# bluetooth_bma400.net
KiCad netlist of a schematic drawn in EAGLE
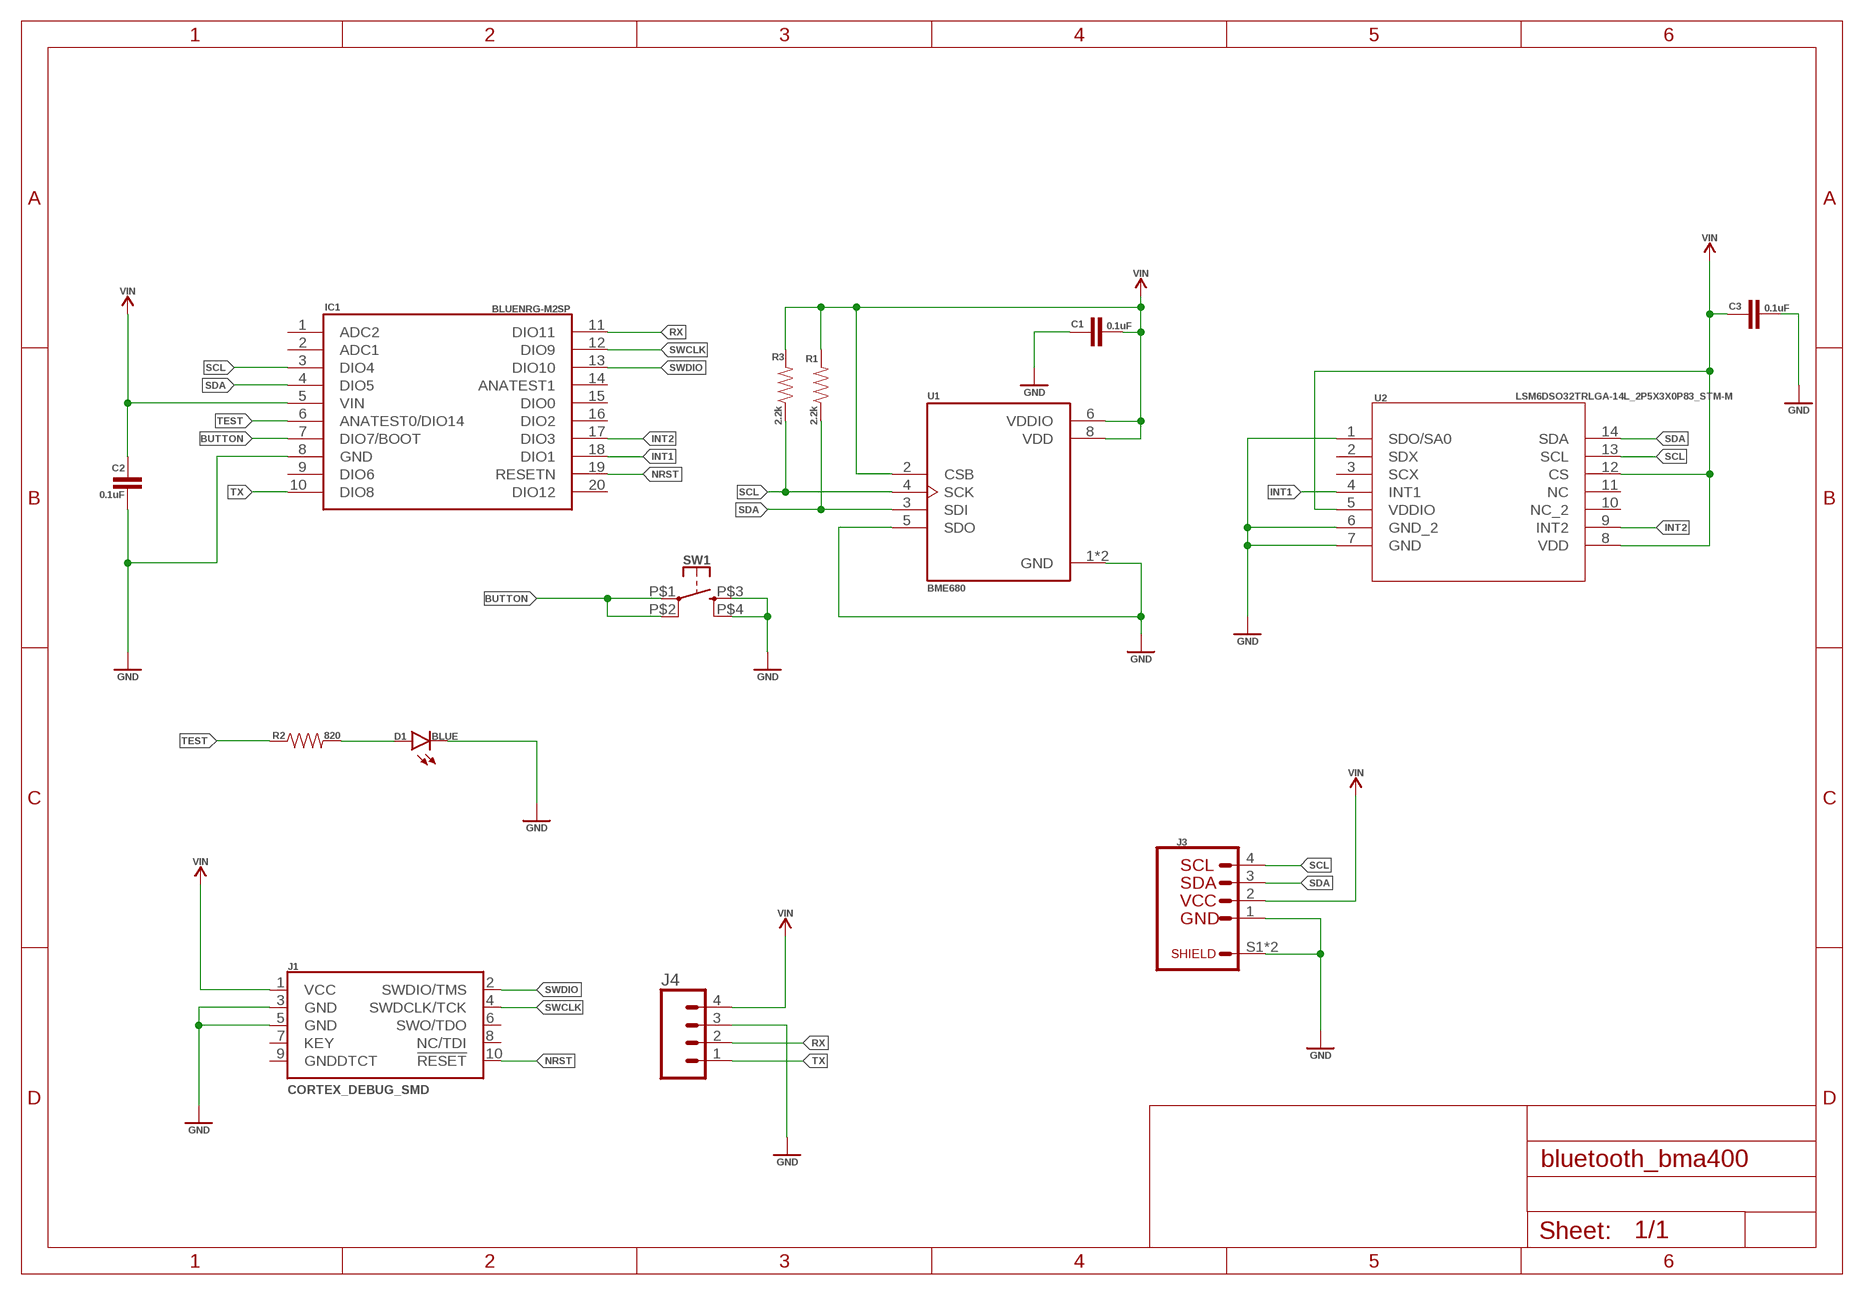
[diagram p0: schematic, sheet 1]

(export (version "E")
  (design (tool "Eeschema 10.0.6"))
  (components
    (comp (ref "C1")
      (value "0.1uF")
      (footprint "eagle-import:0603")
      (libsource (lib "eagle-import") (part "0.1UF-0603-25V-(+80/-20%)"))
    )
    (comp (ref "C2")
      (value "0.1uF")
      (footprint "eagle-import:0603")
      (libsource (lib "eagle-import") (part "0.1UF-0603-25V-(+80/-20%)"))
    )
    (comp (ref "C3")
      (value "0.1uF")
      (footprint "eagle-import:0603")
      (libsource (lib "eagle-import") (part "0.1UF-0603-25V-(+80/-20%)"))
    )
    (comp (ref "D1")
      (value "BLUE")
      (footprint "eagle-import:LED-0603")
      (libsource (lib "eagle-import") (part "LED-BLUE0603"))
    )
    (comp (ref "IC1")
      (value "BLUENRG-M2SP")
      (footprint "eagle-import:BLUENRGM2SP")
      (fields (field (name "MOUSER_PART_NUMBER") "511-BLUENRG-M2SP"))
      (libsource (lib "eagle-import") (part "BLUENRG-M2SP"))
    )
    (comp (ref "J1")
      (value "CORTEX_DEBUG_SMD")
      (footprint "eagle-import:SAMTECH_FTSH-105-01")
      (libsource (lib "eagle-import") (part "CORTEX_DEBUG_SMD"))
    )
    (comp (ref "J3")
      (value "QWIIC")
      (footprint "eagle-import:CONN_BM04B-SRSS-TB(LF)(SN)")
      (libsource (lib "eagle-import") (part "QWIIC"))
    )
    (comp (ref "J4")
      (value "CONN_04SMD")
      (footprint "eagle-import:1X04_SMD_RA_MALE")
      (libsource (lib "eagle-import") (part "CONN_04SMD"))
    )
    (comp (ref "R1")
      (value "2.2k")
      (footprint "eagle-import:0603")
      (libsource (lib "eagle-import") (part "2.2KOHM-0603-1/10W-1%"))
    )
    (comp (ref "R2")
      (value "820")
      (footprint "eagle-import:0603")
      (fields (field (name "SPICEPREFIX") "R"))
      (libsource (lib "eagle-import") (part "8.2KOHM-0603-1/10W-5%"))
    )
    (comp (ref "R3")
      (value "2.2k")
      (footprint "eagle-import:0603")
      (libsource (lib "eagle-import") (part "2.2KOHM-0603-1/10W-1%"))
    )
    (comp (ref "SW1")
      (value "REVERSE_SWITCH")
      (footprint "eagle-import:REVERSE_TACTILE")
      (libsource (lib "eagle-import") (part "REVERSE_SWITCH"))
    )
    (comp (ref "U1")
      (value "BME680")
      (footprint "eagle-import:PSON80P300X300X100-8N")
      (fields (field (name "MF") "Bosch Sensortec"))
      (libsource (lib "eagle-import") (part "BME680"))
    )
    (comp (ref "U2")
      (value "LSM6DSO32TRLGA-14L_2P5X3X0P83_STM-M")
      (footprint "eagle-import:LGA-14L_2P5X3X0P83_STM-M")
      (fields
        (field (name "MANUFACTURER_PART_NUMBER") "LSM6DSO32TR")
        (field (name "COPYRIGHT") "Copyright (C) 2022 Ultra Librarian. All rights reserved.")
      )
      (libsource (lib "eagle-import") (part "LSM6DSO32TRLGA-14L_2P5X3X0P83_STM-M"))
    )
  )
  (nets
    (net (code "1") (name "BUTTON") (class "Default")
      (node (ref "IC1") (pin "7") (pinfunction "DIO7/BOOT_7") (pintype "bidirectional"))
      (node (ref "SW1") (pin "P$1") (pinfunction "1_P$1") (pintype "passive"))
      (node (ref "SW1") (pin "P$2") (pinfunction "2_P$2") (pintype "passive"))
    )
    (net (code "2") (name "GND") (class "Default")
      (node (ref "C1") (pin "1") (pinfunction "1_1") (pintype "passive"))
      (node (ref "C2") (pin "2") (pinfunction "2_2") (pintype "passive"))
      (node (ref "C3") (pin "2") (pinfunction "2_2") (pintype "passive"))
      (node (ref "D1") (pin "C") (pinfunction "C_C") (pintype "passive"))
      (node (ref "IC1") (pin "8") (pinfunction "GND_8") (pintype "bidirectional"))
      (node (ref "J1") (pin "3") (pinfunction "GND_3") (pintype "bidirectional"))
      (node (ref "J1") (pin "5") (pinfunction "GND_5") (pintype "bidirectional"))
      (node (ref "J3") (pin "1") (pinfunction "1_1") (pintype "power_in"))
      (node (ref "J3") (pin "S1") (pinfunction "P$2_S1") (pintype "power_in"))
      (node (ref "J3") (pin "S2") (pinfunction "P$2_S2") (pintype "power_in"))
      (node (ref "J4") (pin "3") (pinfunction "SDA_3") (pintype "passive"))
      (node (ref "SW1") (pin "P$3") (pinfunction "3_P$3") (pintype "passive"))
      (node (ref "SW1") (pin "P$4") (pinfunction "4_P$4") (pintype "passive"))
      (node (ref "U1") (pin "1") (pinfunction "GND_1") (pintype "power_in"))
      (node (ref "U1") (pin "5") (pinfunction "SDO_5") (pintype "bidirectional"))
      (node (ref "U1") (pin "7") (pinfunction "GND_7") (pintype "power_in"))
      (node (ref "U2") (pin "1") (pinfunction "SDO/SA0_1") (pintype "bidirectional"))
      (node (ref "U2") (pin "6") (pinfunction "GND_2_6") (pintype "passive"))
      (node (ref "U2") (pin "7") (pinfunction "GND_7") (pintype "passive"))
    )
    (net (code "3") (name "INT1") (class "Default")
      (node (ref "IC1") (pin "18") (pinfunction "DIO1_18") (pintype "bidirectional"))
      (node (ref "U2") (pin "4") (pinfunction "INT1_4") (pintype "output"))
    )
    (net (code "4") (name "INT2") (class "Default")
      (node (ref "IC1") (pin "17") (pinfunction "DIO3_17") (pintype "bidirectional"))
      (node (ref "U2") (pin "9") (pinfunction "INT2_9") (pintype "output"))
    )
    (net (code "5") (name "NRST") (class "Default")
      (node (ref "IC1") (pin "19") (pinfunction "RESETN_19") (pintype "bidirectional"))
      (node (ref "J1") (pin "10") (pinfunction "~{RESET}_10") (pintype "bidirectional"))
    )
    (net (code "6") (name "Net-(D1-PadA)") (class "Default")
      (node (ref "D1") (pin "A") (pinfunction "A_A") (pintype "passive"))
      (node (ref "R2") (pin "2") (pinfunction "2_2") (pintype "passive"))
    )
    (net (code "7") (name "RX") (class "Default")
      (node (ref "IC1") (pin "11") (pinfunction "DIO11_11") (pintype "bidirectional"))
      (node (ref "J4") (pin "2") (pinfunction "SCL_2") (pintype "passive"))
    )
    (net (code "8") (name "SCL") (class "Default")
      (node (ref "IC1") (pin "3") (pinfunction "DIO4_3") (pintype "bidirectional"))
      (node (ref "J3") (pin "4") (pinfunction "4_4") (pintype "passive"))
      (node (ref "R3") (pin "1") (pinfunction "1_1") (pintype "passive"))
      (node (ref "U1") (pin "4") (pinfunction "SCK_4") (pintype "input"))
      (node (ref "U2") (pin "13") (pinfunction "SCL_13") (pintype "input"))
    )
    (net (code "9") (name "SDA") (class "Default")
      (node (ref "IC1") (pin "4") (pinfunction "DIO5_4") (pintype "bidirectional"))
      (node (ref "J3") (pin "3") (pinfunction "3_3") (pintype "passive"))
      (node (ref "R1") (pin "1") (pinfunction "1_1") (pintype "passive"))
      (node (ref "U1") (pin "3") (pinfunction "SDI_3") (pintype "bidirectional"))
      (node (ref "U2") (pin "14") (pinfunction "SDA_14") (pintype "bidirectional"))
    )
    (net (code "10") (name "SWCLK") (class "Default")
      (node (ref "IC1") (pin "12") (pinfunction "DIO9_12") (pintype "bidirectional"))
      (node (ref "J1") (pin "4") (pinfunction "SWDCLK/TCK_4") (pintype "bidirectional"))
    )
    (net (code "11") (name "SWDIO") (class "Default")
      (node (ref "IC1") (pin "13") (pinfunction "DIO10_13") (pintype "bidirectional"))
      (node (ref "J1") (pin "2") (pinfunction "SWDIO/TMS_2") (pintype "bidirectional"))
    )
    (net (code "12") (name "TEST") (class "Default")
      (node (ref "IC1") (pin "6") (pinfunction "ANATEST0/DIO14_6") (pintype "bidirectional"))
      (node (ref "R2") (pin "1") (pinfunction "1_1") (pintype "passive"))
    )
    (net (code "13") (name "TX") (class "Default")
      (node (ref "IC1") (pin "10") (pinfunction "DIO8_10") (pintype "bidirectional"))
      (node (ref "J4") (pin "1") (pinfunction "VCC_1") (pintype "passive"))
    )
    (net (code "14") (name "VIN") (class "Default")
      (node (ref "C1") (pin "2") (pinfunction "2_2") (pintype "passive"))
      (node (ref "C2") (pin "1") (pinfunction "1_1") (pintype "passive"))
      (node (ref "C3") (pin "1") (pinfunction "1_1") (pintype "passive"))
      (node (ref "IC1") (pin "5") (pinfunction "VIN_5") (pintype "bidirectional"))
      (node (ref "J1") (pin "1") (pinfunction "VCC_1") (pintype "bidirectional"))
      (node (ref "J3") (pin "2") (pinfunction "2_2") (pintype "power_in"))
      (node (ref "J4") (pin "4") (pinfunction "GND_4") (pintype "passive"))
      (node (ref "R1") (pin "2") (pinfunction "2_2") (pintype "passive"))
      (node (ref "R3") (pin "2") (pinfunction "2_2") (pintype "passive"))
      (node (ref "U1") (pin "2") (pinfunction "CSB_2") (pintype "input"))
      (node (ref "U1") (pin "6") (pinfunction "VDDIO_6") (pintype "power_in"))
      (node (ref "U1") (pin "8") (pinfunction "VDD_8") (pintype "power_in"))
      (node (ref "U2") (pin "12") (pinfunction "CS_12") (pintype "input"))
      (node (ref "U2") (pin "5") (pinfunction "VDDIO_5") (pintype "power_in"))
      (node (ref "U2") (pin "8") (pinfunction "VDD_8") (pintype "power_in"))
    )
    (net (code "15") (name "unconnected-(IC1-ADC1-Pad2)") (class "Default")
      (node (ref "IC1") (pin "2") (pinfunction "ADC1_2") (pintype "bidirectional"))
    )
    (net (code "16") (name "unconnected-(IC1-ADC2-Pad1)") (class "Default")
      (node (ref "IC1") (pin "1") (pinfunction "ADC2_1") (pintype "bidirectional"))
    )
    (net (code "17") (name "unconnected-(IC1-ANATEST1-Pad14)") (class "Default")
      (node (ref "IC1") (pin "14") (pinfunction "ANATEST1_14") (pintype "bidirectional"))
    )
    (net (code "18") (name "unconnected-(IC1-DIO0-Pad15)") (class "Default")
      (node (ref "IC1") (pin "15") (pinfunction "DIO0_15") (pintype "bidirectional"))
    )
    (net (code "19") (name "unconnected-(IC1-DIO2-Pad16)") (class "Default")
      (node (ref "IC1") (pin "16") (pinfunction "DIO2_16") (pintype "bidirectional"))
    )
    (net (code "20") (name "unconnected-(IC1-DIO6-Pad9)") (class "Default")
      (node (ref "IC1") (pin "9") (pinfunction "DIO6_9") (pintype "bidirectional"))
    )
    (net (code "21") (name "unconnected-(IC1-DIO12-Pad20)") (class "Default")
      (node (ref "IC1") (pin "20") (pinfunction "DIO12_20") (pintype "bidirectional"))
    )
    (net (code "22") (name "unconnected-(J1-GNDDTCT-Pad9)") (class "Default")
      (node (ref "J1") (pin "9") (pinfunction "GNDDTCT_9") (pintype "bidirectional"))
    )
    (net (code "23") (name "unconnected-(J1-KEY-Pad7)") (class "Default")
      (node (ref "J1") (pin "7") (pinfunction "KEY_7") (pintype "bidirectional"))
    )
    (net (code "24") (name "unconnected-(J1-NC{slash}TDI-Pad8)") (class "Default")
      (node (ref "J1") (pin "8") (pinfunction "NC/TDI_8") (pintype "bidirectional"))
    )
    (net (code "25") (name "unconnected-(J1-SWO{slash}TDO-Pad6)") (class "Default")
      (node (ref "J1") (pin "6") (pinfunction "SWO/TDO_6") (pintype "bidirectional"))
    )
    (net (code "26") (name "unconnected-(U2-NC-Pad11)") (class "Default")
      (node (ref "U2") (pin "11") (pinfunction "NC_11") (pintype "no_connect"))
    )
    (net (code "27") (name "unconnected-(U2-NC_2-Pad10)") (class "Default")
      (node (ref "U2") (pin "10") (pinfunction "NC_2_10") (pintype "no_connect"))
    )
    (net (code "28") (name "unconnected-(U2-SCX-Pad3)") (class "Default")
      (node (ref "U2") (pin "3") (pinfunction "SCX_3") (pintype "passive"))
    )
    (net (code "29") (name "unconnected-(U2-SDX-Pad2)") (class "Default")
      (node (ref "U2") (pin "2") (pinfunction "SDX_2") (pintype "passive"))
    )
  )
)
